# etapa4.net
KiCad netlist of a schematic drawn in Altium Designer
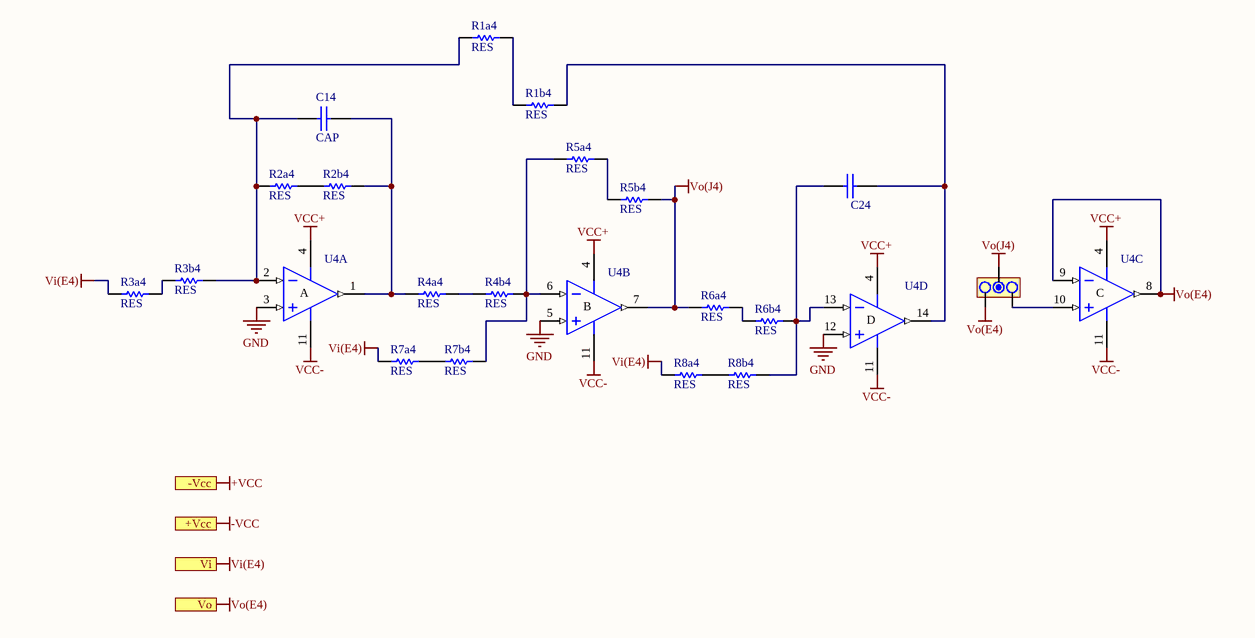
[diagram p0: etapa4.SchDoc]

(export (version "E")
  (design (tool "Eeschema 10.0.6"))
  (components
    (comp (ref "C14") (value "CAP") (footprint "CAP200") (libsource (lib "LIBEBAL") (part "CAP")))
    (comp (ref "C24") (value "CAP") (footprint "CAP200") (libsource (lib "LIBEBAL") (part "CAP")))
    (comp (ref "Jumper4") (value "JUMPER") (footprint "JUMPER3") (libsource (lib "LIBEBAL") (part "JUMPER3")))
    (comp (ref "R1a4") (value "RES") (footprint "0805") (libsource (lib "LIBEBAL") (part "RES")))
    (comp (ref "R1b4") (value "RES") (footprint "0805") (libsource (lib "LIBEBAL") (part "RES")))
    (comp (ref "R2a4") (value "RES") (footprint "0805") (libsource (lib "LIBEBAL") (part "RES")))
    (comp (ref "R2b4") (value "RES") (footprint "0805") (libsource (lib "LIBEBAL") (part "RES")))
    (comp (ref "R3a4") (value "RES") (footprint "0805") (libsource (lib "LIBEBAL") (part "RES")))
    (comp (ref "R3b4") (value "RES") (footprint "0805") (libsource (lib "LIBEBAL") (part "RES")))
    (comp (ref "R4a4") (value "RES") (footprint "0805") (libsource (lib "LIBEBAL") (part "RES")))
    (comp (ref "R4b4") (value "RES") (footprint "0805") (libsource (lib "LIBEBAL") (part "RES")))
    (comp (ref "R5a4") (value "RES") (footprint "0805") (libsource (lib "LIBEBAL") (part "RES")))
    (comp (ref "R5b4") (value "RES") (footprint "0805") (libsource (lib "LIBEBAL") (part "RES")))
    (comp (ref "R6a4") (value "RES") (footprint "0805") (libsource (lib "LIBEBAL") (part "RES")))
    (comp (ref "R6b4") (value "RES") (footprint "0805") (libsource (lib "LIBEBAL") (part "RES")))
    (comp (ref "R7a4") (value "RES") (footprint "0805") (libsource (lib "LIBEBAL") (part "RES")))
    (comp (ref "R7b4") (value "RES") (footprint "0805") (libsource (lib "LIBEBAL") (part "RES")))
    (comp (ref "R8a4") (value "RES") (footprint "0805") (libsource (lib "LIBEBAL") (part "RES")))
    (comp (ref "R8b4") (value "RES") (footprint "0805") (libsource (lib "LIBEBAL") (part "RES")))
    (comp (ref "U4")
      (value "TL084N")
      (footprint "N014")
      (description "JFET-Input Operational Amplifier")
      (fields (field (name "PUBLISHER") "Altium Limited"))
      (libsource (lib "TI Operational Amplifier") (part "TL084N"))
    )
  )
  (nets
    (net (code "3") (name "GND") (class "Default")
      (node (ref "U4") (pin "12") (pinfunction "IN+_12") (pintype "input"))
      (node (ref "U4") (pin "3") (pinfunction "IN+_3") (pintype "input"))
      (node (ref "U4") (pin "5") (pinfunction "IN+_5") (pintype "input"))
    )
    (net (code "4") (name "Net-(R1a4-Pad2)") (class "Default")
      (node (ref "R1a4") (pin "2") (pinfunction "2_2") (pintype "passive"))
      (node (ref "R1b4") (pin "1") (pinfunction "1_1") (pintype "passive"))
    )
    (net (code "5") (name "Net-(R2a4-Pad2)") (class "Default")
      (node (ref "R2a4") (pin "2") (pinfunction "2_2") (pintype "passive"))
      (node (ref "R2b4") (pin "1") (pinfunction "1_1") (pintype "passive"))
    )
    (net (code "6") (name "Net-(R3a4-Pad2)") (class "Default")
      (node (ref "R3a4") (pin "2") (pinfunction "2_2") (pintype "passive"))
      (node (ref "R3b4") (pin "1") (pinfunction "1_1") (pintype "passive"))
    )
    (net (code "7") (name "Net-(R4a4-Pad2)") (class "Default")
      (node (ref "R4a4") (pin "2") (pinfunction "2_2") (pintype "passive"))
      (node (ref "R4b4") (pin "1") (pinfunction "1_1") (pintype "passive"))
    )
    (net (code "8") (name "Net-(R5a4-Pad2)") (class "Default")
      (node (ref "R5a4") (pin "2") (pinfunction "2_2") (pintype "passive"))
      (node (ref "R5b4") (pin "1") (pinfunction "1_1") (pintype "passive"))
    )
    (net (code "9") (name "Net-(R6a4-Pad2)") (class "Default")
      (node (ref "R6a4") (pin "2") (pinfunction "2_2") (pintype "passive"))
      (node (ref "R6b4") (pin "1") (pinfunction "1_1") (pintype "passive"))
    )
    (net (code "10") (name "Net-(R7a4-Pad2)") (class "Default")
      (node (ref "R7a4") (pin "2") (pinfunction "2_2") (pintype "passive"))
      (node (ref "R7b4") (pin "1") (pinfunction "1_1") (pintype "passive"))
    )
    (net (code "11") (name "Net-(R8a4-Pad2)") (class "Default")
      (node (ref "R8a4") (pin "2") (pinfunction "2_2") (pintype "passive"))
      (node (ref "R8b4") (pin "1") (pinfunction "1_1") (pintype "passive"))
    )
    (net (code "12") (name "Net-(U4A-IN-)") (class "Default")
      (node (ref "C14") (pin "1") (pinfunction "1_1") (pintype "passive"))
      (node (ref "R1a4") (pin "1") (pinfunction "1_1") (pintype "passive"))
      (node (ref "R2a4") (pin "1") (pinfunction "1_1") (pintype "passive"))
      (node (ref "R3b4") (pin "2") (pinfunction "2_2") (pintype "passive"))
      (node (ref "U4") (pin "2") (pinfunction "IN-_2") (pintype "input"))
    )
    (net (code "13") (name "Net-(U4A-OUT)") (class "Default")
      (node (ref "C14") (pin "2") (pinfunction "2_2") (pintype "passive"))
      (node (ref "R2b4") (pin "2") (pinfunction "2_2") (pintype "passive"))
      (node (ref "R4a4") (pin "1") (pinfunction "1_1") (pintype "passive"))
      (node (ref "U4") (pin "1") (pinfunction "OUT_1") (pintype "output"))
    )
    (net (code "14") (name "Net-(U4B-IN-)") (class "Default")
      (node (ref "R4b4") (pin "2") (pinfunction "2_2") (pintype "passive"))
      (node (ref "R5a4") (pin "1") (pinfunction "1_1") (pintype "passive"))
      (node (ref "R7b4") (pin "2") (pinfunction "2_2") (pintype "passive"))
      (node (ref "U4") (pin "6") (pinfunction "IN-_6") (pintype "input"))
    )
    (net (code "15") (name "Net-(U4C-IN+)") (class "Default")
      (node (ref "Jumper4") (pin "1") (pinfunction "1_1") (pintype "passive"))
      (node (ref "U4") (pin "10") (pinfunction "IN+_10") (pintype "input"))
    )
    (net (code "16") (name "Net-(U4D-IN-)") (class "Default")
      (node (ref "C24") (pin "1") (pinfunction "1_1") (pintype "passive"))
      (node (ref "R6b4") (pin "2") (pinfunction "2_2") (pintype "passive"))
      (node (ref "R8b4") (pin "2") (pinfunction "2_2") (pintype "passive"))
      (node (ref "U4") (pin "13") (pinfunction "IN-_13") (pintype "input"))
    )
    (net (code "17") (name "Net-(U4D-OUT)") (class "Default")
      (node (ref "C24") (pin "2") (pinfunction "2_2") (pintype "passive"))
      (node (ref "R1b4") (pin "2") (pinfunction "2_2") (pintype "passive"))
      (node (ref "U4") (pin "14") (pinfunction "OUT_14") (pintype "output"))
    )
    (net (code "18") (name "VCC+") (class "Default")
      (node (ref "U4") (pin "4") (pinfunction "V+_4") (pintype "power_in"))
    )
    (net (code "19") (name "VCC-") (class "Default")
      (node (ref "U4") (pin "11") (pinfunction "V-_11") (pintype "power_in"))
    )
    (net (code "20") (name "Vi(E4)") (class "Default")
      (node (ref "R3a4") (pin "1") (pinfunction "1_1") (pintype "passive"))
      (node (ref "R7a4") (pin "1") (pinfunction "1_1") (pintype "passive"))
      (node (ref "R8a4") (pin "1") (pinfunction "1_1") (pintype "passive"))
    )
    (net (code "21") (name "Vo(E4)") (class "Default")
      (node (ref "Jumper4") (pin "3") (pinfunction "3_3") (pintype "passive"))
      (node (ref "U4") (pin "8") (pinfunction "OUT_8") (pintype "output"))
      (node (ref "U4") (pin "9") (pinfunction "IN-_9") (pintype "input"))
    )
    (net (code "22") (name "Vo(J4)") (class "Default")
      (node (ref "Jumper4") (pin "2") (pinfunction "2_2") (pintype "passive"))
      (node (ref "R5b4") (pin "2") (pinfunction "2_2") (pintype "passive"))
      (node (ref "R6a4") (pin "1") (pinfunction "1_1") (pintype "passive"))
      (node (ref "U4") (pin "7") (pinfunction "OUT_7") (pintype "output"))
    )
  )
)
